# devkit.net
KiCad netlist of a schematic drawn in EAGLE
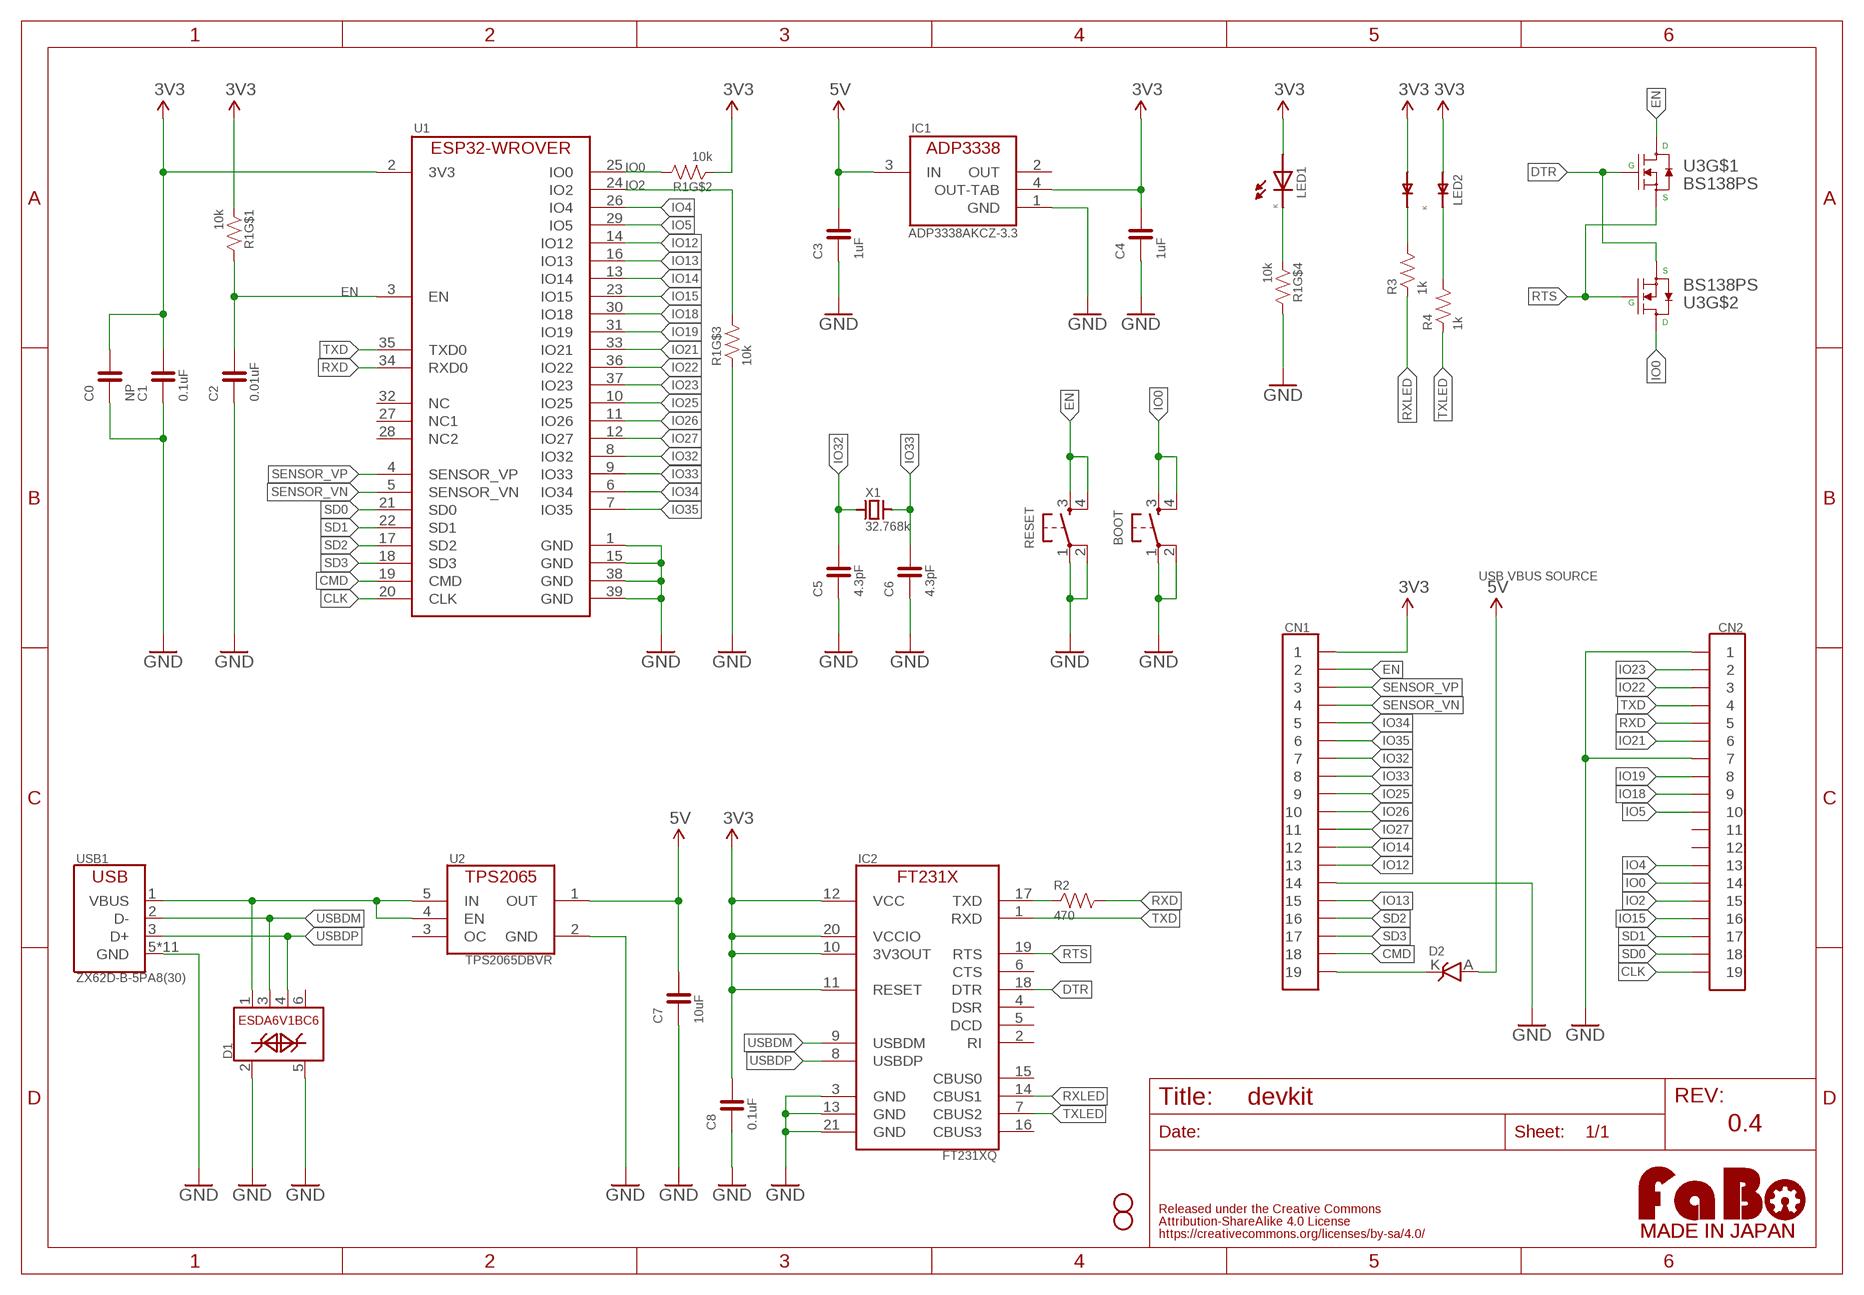
[diagram p0: schematic, sheet 1]

(export (version "E")
  (design (tool "Eeschema 10.0.6"))
  (components
    (comp (ref "BOOT")
      (value "TACTILE-KMR2")
      (footprint "eagle-import:KMR2-TACT")
      (libsource (lib "eagle-import") (part "TACTILE-KMR2"))
    )
    (comp (ref "C0")
      (value "NP")
      (footprint "eagle-import:MULTIPAD0603")
      (libsource (lib "eagle-import") (part "CAPACITOR-M"))
    )
    (comp (ref "C1")
      (value "0.1uF")
      (footprint "eagle-import:EIA0603")
      (libsource (lib "eagle-import") (part "CAPACITOR-0603"))
    )
    (comp (ref "C2")
      (value "0.01uF")
      (footprint "eagle-import:EIA0603")
      (libsource (lib "eagle-import") (part "CAPACITOR-0603"))
    )
    (comp (ref "C3")
      (value "1uF")
      (footprint "eagle-import:EIA0603")
      (libsource (lib "eagle-import") (part "CAPACITOR-0603"))
    )
    (comp (ref "C4")
      (value "1uF")
      (footprint "eagle-import:EIA0603")
      (libsource (lib "eagle-import") (part "CAPACITOR-0603"))
    )
    (comp (ref "C5")
      (value "4.3pF")
      (footprint "eagle-import:EIA0603")
      (libsource (lib "eagle-import") (part "CAPACITOR-0603"))
    )
    (comp (ref "C6")
      (value "4.3pF")
      (footprint "eagle-import:EIA0603")
      (libsource (lib "eagle-import") (part "CAPACITOR-0603"))
    )
    (comp (ref "C7")
      (value "10uF")
      (footprint "eagle-import:EIA0603")
      (libsource (lib "eagle-import") (part "CAPACITOR-0603"))
    )
    (comp (ref "C8")
      (value "0.1uF")
      (footprint "eagle-import:EIA0603")
      (libsource (lib "eagle-import") (part "CAPACITOR-0603"))
    )
    (comp (ref "CN1")
      (value "PIN_1X19")
      (footprint "eagle-import:PIN_1X19")
      (libsource (lib "eagle-import") (part "PIN_1X19"))
    )
    (comp (ref "CN2")
      (value "PIN_1X19")
      (footprint "eagle-import:PIN_1X19")
      (libsource (lib "eagle-import") (part "PIN_1X19"))
    )
    (comp (ref "D1")
      (value "ESDA6V1BC6")
      (footprint "eagle-import:SOT-23-6L")
      (libsource (lib "eagle-import") (part "ESDA6V1BC6"))
    )
    (comp (ref "D2")
      (value "DIODE_SCHOTTKY-RB161MM-20")
      (footprint "eagle-import:SOD-123FL_RB161MM-20")
      (libsource (lib "eagle-import") (part "DIODE_SCHOTTKY-RB161MM-20"))
    )
    (comp (ref "FID1")
      (value "FIDUCIAL-TOP")
      (footprint "eagle-import:FIDUCIAL_15_TOP")
      (libsource (lib "eagle-import") (part "FIDUCIAL-TOP"))
    )
    (comp (ref "FID2")
      (value "FIDUCIAL-TOP")
      (footprint "eagle-import:FIDUCIAL_15_TOP")
      (libsource (lib "eagle-import") (part "FIDUCIAL-TOP"))
    )
    (comp (ref "IC1")
      (value "ADP3338AKCZ-3.3")
      (footprint "eagle-import:SOT-223-KC3")
      (libsource (lib "eagle-import") (part "ADP3338AKCZ"))
    )
    (comp (ref "IC2")
      (value "FT231XQ")
      (footprint "eagle-import:QFN-20")
      (libsource (lib "eagle-import") (part "FT231XQ"))
    )
    (comp (ref "LED1")
      (value "LED-0603")
      (footprint "eagle-import:LED_0603")
      (libsource (lib "eagle-import") (part "LED-0603"))
    )
    (comp (ref "LED2")
      (value "HSMF-C16X")
      (footprint "eagle-import:HSMF-C16X")
      (libsource (lib "eagle-import") (part "HSMF-C16X"))
    )
    (comp (ref "LOGO1")
      (value "LOGO_FABO-M_BOTTOM")
      (footprint "eagle-import:LOGO_FABO_M_BOTTOM")
      (libsource (lib "eagle-import") (part "LOGO_FABO-M_BOTTOM"))
    )
    (comp (ref "R1")
      (value "10k")
      (footprint "eagle-import:EXBV8V")
      (libsource (lib "eagle-import") (part "RESISTOR_ARRAY"))
    )
    (comp (ref "R2")
      (value "470")
      (footprint "eagle-import:EIA0603")
      (libsource (lib "eagle-import") (part "RESISTOR-0603"))
    )
    (comp (ref "R3")
      (value "1k")
      (footprint "eagle-import:EIA0603")
      (libsource (lib "eagle-import") (part "RESISTOR-0603"))
    )
    (comp (ref "R4")
      (value "1k")
      (footprint "eagle-import:EIA0603")
      (libsource (lib "eagle-import") (part "RESISTOR-0603"))
    )
    (comp (ref "RESET")
      (value "TACTILE-KMR2")
      (footprint "eagle-import:KMR2-TACT")
      (libsource (lib "eagle-import") (part "TACTILE-KMR2"))
    )
    (comp (ref "U1")
      (value "ESP32-WROVER-B")
      (footprint "eagle-import:ESP32-WROVER-B")
      (libsource (lib "eagle-import") (part "ESP32-WROVER-B"))
    )
    (comp (ref "U2")
      (value "TPS2065DBVR")
      (footprint "eagle-import:SOT-23-5")
      (libsource (lib "eagle-import") (part "TPS2065DBV"))
    )
    (comp (ref "U3")
      (value "BS138PS")
      (footprint "eagle-import:SOT-363")
      (libsource (lib "eagle-import") (part "BS138PS"))
    )
    (comp (ref "USB1")
      (value "ZX62D-B-5PA8(30)")
      (footprint "eagle-import:ZX62D-B-5PA8")
      (libsource (lib "eagle-import") (part "USB-ZX62D"))
    )
    (comp (ref "X1")
      (value "32.768k")
      (footprint "eagle-import:ABS07")
      (libsource (lib "eagle-import") (part "CRYSTAL-ABS07"))
    )
  )
  (nets
    (net (code "1") (name "3V3") (class "Default")
      (node (ref "C0") (pin "2") (pinfunction "2_2") (pintype "passive"))
      (node (ref "C1") (pin "2") (pinfunction "2_2") (pintype "passive"))
      (node (ref "C4") (pin "2") (pinfunction "2_2") (pintype "passive"))
      (node (ref "C8") (pin "2") (pinfunction "2_2") (pintype "passive"))
      (node (ref "CN1") (pin "1") (pinfunction "1_1") (pintype "bidirectional"))
      (node (ref "IC1") (pin "4") (pinfunction "OUT-TAB_4") (pintype "bidirectional"))
      (node (ref "IC2") (pin "10") (pinfunction "3V3OUT_10") (pintype "bidirectional"))
      (node (ref "IC2") (pin "11") (pinfunction "RESET_11") (pintype "bidirectional"))
      (node (ref "IC2") (pin "12") (pinfunction "VCC_12") (pintype "bidirectional"))
      (node (ref "IC2") (pin "20") (pinfunction "VCCIO_20") (pintype "bidirectional"))
      (node (ref "LED1") (pin "A") (pinfunction "ANODE_A") (pintype "passive"))
      (node (ref "LED2") (pin "1") (pinfunction "A1_1") (pintype "passive"))
      (node (ref "LED2") (pin "2") (pinfunction "A2_2") (pintype "bidirectional"))
      (node (ref "R1") (pin "1") (pinfunction "1_1") (pintype "bidirectional"))
      (node (ref "R1") (pin "2") (pinfunction "1_2") (pintype "bidirectional"))
      (node (ref "U1") (pin "2") (pinfunction "3V3_2") (pintype "bidirectional"))
    )
    (net (code "2") (name "5V") (class "Default")
      (node (ref "C3") (pin "2") (pinfunction "2_2") (pintype "passive"))
      (node (ref "C7") (pin "2") (pinfunction "2_2") (pintype "passive"))
      (node (ref "D2") (pin "A") (pinfunction "A_A") (pintype "bidirectional"))
      (node (ref "IC1") (pin "3") (pinfunction "IN_3") (pintype "bidirectional"))
      (node (ref "U2") (pin "1") (pinfunction "OUT_1") (pintype "bidirectional"))
    )
    (net (code "3") (name "CLK") (class "Default")
      (node (ref "CN2") (pin "19") (pinfunction "19_19") (pintype "bidirectional"))
      (node (ref "U1") (pin "20") (pinfunction "CLK_20") (pintype "bidirectional"))
    )
    (net (code "4") (name "CMD") (class "Default")
      (node (ref "CN1") (pin "18") (pinfunction "18_18") (pintype "bidirectional"))
      (node (ref "U1") (pin "19") (pinfunction "CMD_19") (pintype "bidirectional"))
    )
    (net (code "5") (name "DTR") (class "Default")
      (node (ref "IC2") (pin "18") (pinfunction "DTR_18") (pintype "bidirectional"))
      (node (ref "U3") (pin "2") (pinfunction "G_2") (pintype "passive"))
      (node (ref "U3") (pin "4") (pinfunction "S_4") (pintype "passive"))
    )
    (net (code "6") (name "EN") (class "Default")
      (node (ref "C2") (pin "2") (pinfunction "2_2") (pintype "passive"))
      (node (ref "CN1") (pin "2") (pinfunction "2_2") (pintype "bidirectional"))
      (node (ref "R1") (pin "8") (pinfunction "2_8") (pintype "bidirectional"))
      (node (ref "RESET") (pin "3") (pinfunction "3_3") (pintype "passive"))
      (node (ref "RESET") (pin "4") (pinfunction "4_4") (pintype "passive"))
      (node (ref "U1") (pin "3") (pinfunction "EN_3") (pintype "bidirectional"))
      (node (ref "U3") (pin "6") (pinfunction "D_6") (pintype "passive"))
    )
    (net (code "7") (name "GND") (class "Default")
      (node (ref "BOOT") (pin "1") (pinfunction "1_1") (pintype "passive"))
      (node (ref "BOOT") (pin "2") (pinfunction "2_2") (pintype "passive"))
      (node (ref "C0") (pin "1") (pinfunction "1_1") (pintype "passive"))
      (node (ref "C1") (pin "1") (pinfunction "1_1") (pintype "passive"))
      (node (ref "C2") (pin "1") (pinfunction "1_1") (pintype "passive"))
      (node (ref "C3") (pin "1") (pinfunction "1_1") (pintype "passive"))
      (node (ref "C4") (pin "1") (pinfunction "1_1") (pintype "passive"))
      (node (ref "C5") (pin "1") (pinfunction "1_1") (pintype "passive"))
      (node (ref "C6") (pin "1") (pinfunction "1_1") (pintype "passive"))
      (node (ref "C7") (pin "1") (pinfunction "1_1") (pintype "passive"))
      (node (ref "C8") (pin "1") (pinfunction "1_1") (pintype "passive"))
      (node (ref "CN1") (pin "14") (pinfunction "14_14") (pintype "bidirectional"))
      (node (ref "CN2") (pin "1") (pinfunction "1_1") (pintype "bidirectional"))
      (node (ref "CN2") (pin "7") (pinfunction "7_7") (pintype "bidirectional"))
      (node (ref "D1") (pin "2") (pinfunction "2_2") (pintype "bidirectional"))
      (node (ref "D1") (pin "5") (pinfunction "5_5") (pintype "bidirectional"))
      (node (ref "IC1") (pin "1") (pinfunction "GND_1") (pintype "bidirectional"))
      (node (ref "IC2") (pin "13") (pinfunction "GND_13") (pintype "bidirectional"))
      (node (ref "IC2") (pin "21") (pinfunction "GND_21") (pintype "bidirectional"))
      (node (ref "IC2") (pin "3") (pinfunction "GND_3") (pintype "bidirectional"))
      (node (ref "R1") (pin "3") (pinfunction "1_3") (pintype "bidirectional"))
      (node (ref "R1") (pin "5") (pinfunction "2_5") (pintype "bidirectional"))
      (node (ref "RESET") (pin "1") (pinfunction "1_1") (pintype "passive"))
      (node (ref "RESET") (pin "2") (pinfunction "2_2") (pintype "passive"))
      (node (ref "U1") (pin "1") (pinfunction "GND_1") (pintype "bidirectional"))
      (node (ref "U1") (pin "15") (pinfunction "GND_15") (pintype "bidirectional"))
      (node (ref "U1") (pin "38") (pinfunction "GND_38") (pintype "bidirectional"))
      (node (ref "U1") (pin "39") (pinfunction "GND_39") (pintype "bidirectional"))
      (node (ref "U2") (pin "2") (pinfunction "GND_2") (pintype "bidirectional"))
      (node (ref "USB1") (pin "5") (pinfunction "GND_5") (pintype "bidirectional"))
      (node (ref "USB1") (pin "B1") (pinfunction "GND_B1") (pintype "bidirectional"))
      (node (ref "USB1") (pin "B2") (pinfunction "GND_B2") (pintype "bidirectional"))
      (node (ref "USB1") (pin "B3") (pinfunction "GND_B3") (pintype "bidirectional"))
      (node (ref "USB1") (pin "B4") (pinfunction "GND_B4") (pintype "bidirectional"))
      (node (ref "USB1") (pin "T1") (pinfunction "GND_T1") (pintype "bidirectional"))
      (node (ref "USB1") (pin "T2") (pinfunction "GND_T2") (pintype "bidirectional"))
      (node (ref "USB1") (pin "T3") (pinfunction "GND_T3") (pintype "bidirectional"))
      (node (ref "USB1") (pin "T4") (pinfunction "GND_T4") (pintype "bidirectional"))
      (node (ref "USB1") (pin "T5") (pinfunction "GND_T5") (pintype "bidirectional"))
      (node (ref "USB1") (pin "T6") (pinfunction "GND_T6") (pintype "bidirectional"))
    )
    (net (code "8") (name "IO0") (class "Default")
      (node (ref "BOOT") (pin "3") (pinfunction "3_3") (pintype "passive"))
      (node (ref "BOOT") (pin "4") (pinfunction "4_4") (pintype "passive"))
      (node (ref "CN2") (pin "14") (pinfunction "14_14") (pintype "bidirectional"))
      (node (ref "R1") (pin "7") (pinfunction "2_7") (pintype "bidirectional"))
      (node (ref "U1") (pin "25") (pinfunction "IO0_25") (pintype "bidirectional"))
      (node (ref "U3") (pin "3") (pinfunction "D_3") (pintype "passive"))
    )
    (net (code "9") (name "IO2") (class "Default")
      (node (ref "CN2") (pin "15") (pinfunction "15_15") (pintype "bidirectional"))
      (node (ref "R1") (pin "6") (pinfunction "2_6") (pintype "bidirectional"))
      (node (ref "U1") (pin "24") (pinfunction "IO2_24") (pintype "bidirectional"))
    )
    (net (code "10") (name "IO4") (class "Default")
      (node (ref "CN2") (pin "13") (pinfunction "13_13") (pintype "bidirectional"))
      (node (ref "U1") (pin "26") (pinfunction "IO4_26") (pintype "bidirectional"))
    )
    (net (code "11") (name "IO5") (class "Default")
      (node (ref "CN2") (pin "10") (pinfunction "10_10") (pintype "bidirectional"))
      (node (ref "U1") (pin "29") (pinfunction "IO5_29") (pintype "bidirectional"))
    )
    (net (code "12") (name "IO12") (class "Default")
      (node (ref "CN1") (pin "13") (pinfunction "13_13") (pintype "bidirectional"))
      (node (ref "U1") (pin "14") (pinfunction "IO12_14") (pintype "bidirectional"))
    )
    (net (code "13") (name "IO13") (class "Default")
      (node (ref "CN1") (pin "15") (pinfunction "15_15") (pintype "bidirectional"))
      (node (ref "U1") (pin "16") (pinfunction "IO13_16") (pintype "bidirectional"))
    )
    (net (code "14") (name "IO14") (class "Default")
      (node (ref "CN1") (pin "12") (pinfunction "12_12") (pintype "bidirectional"))
      (node (ref "U1") (pin "13") (pinfunction "IO14_13") (pintype "bidirectional"))
    )
    (net (code "15") (name "IO15") (class "Default")
      (node (ref "CN2") (pin "16") (pinfunction "16_16") (pintype "bidirectional"))
      (node (ref "U1") (pin "23") (pinfunction "IO15_23") (pintype "bidirectional"))
    )
    (net (code "16") (name "IO18") (class "Default")
      (node (ref "CN2") (pin "9") (pinfunction "9_9") (pintype "bidirectional"))
      (node (ref "U1") (pin "30") (pinfunction "IO18_30") (pintype "bidirectional"))
    )
    (net (code "17") (name "IO19") (class "Default")
      (node (ref "CN2") (pin "8") (pinfunction "8_8") (pintype "bidirectional"))
      (node (ref "U1") (pin "31") (pinfunction "IO19_31") (pintype "bidirectional"))
    )
    (net (code "18") (name "IO21") (class "Default")
      (node (ref "CN2") (pin "6") (pinfunction "6_6") (pintype "bidirectional"))
      (node (ref "U1") (pin "33") (pinfunction "IO21_33") (pintype "bidirectional"))
    )
    (net (code "19") (name "IO22") (class "Default")
      (node (ref "CN2") (pin "3") (pinfunction "3_3") (pintype "bidirectional"))
      (node (ref "U1") (pin "36") (pinfunction "IO22_36") (pintype "bidirectional"))
    )
    (net (code "20") (name "IO23") (class "Default")
      (node (ref "CN2") (pin "2") (pinfunction "2_2") (pintype "bidirectional"))
      (node (ref "U1") (pin "37") (pinfunction "IO23_37") (pintype "bidirectional"))
    )
    (net (code "21") (name "IO25") (class "Default")
      (node (ref "CN1") (pin "9") (pinfunction "9_9") (pintype "bidirectional"))
      (node (ref "U1") (pin "10") (pinfunction "IO25_10") (pintype "bidirectional"))
    )
    (net (code "22") (name "IO26") (class "Default")
      (node (ref "CN1") (pin "10") (pinfunction "10_10") (pintype "bidirectional"))
      (node (ref "U1") (pin "11") (pinfunction "IO26_11") (pintype "bidirectional"))
    )
    (net (code "23") (name "IO27") (class "Default")
      (node (ref "CN1") (pin "11") (pinfunction "11_11") (pintype "bidirectional"))
      (node (ref "U1") (pin "12") (pinfunction "IO27_12") (pintype "bidirectional"))
    )
    (net (code "24") (name "IO32") (class "Default")
      (node (ref "C5") (pin "2") (pinfunction "2_2") (pintype "passive"))
      (node (ref "CN1") (pin "7") (pinfunction "7_7") (pintype "bidirectional"))
      (node (ref "U1") (pin "8") (pinfunction "IO32_8") (pintype "bidirectional"))
      (node (ref "X1") (pin "1") (pinfunction "P$1_1") (pintype "bidirectional"))
    )
    (net (code "25") (name "IO33") (class "Default")
      (node (ref "C6") (pin "2") (pinfunction "2_2") (pintype "passive"))
      (node (ref "CN1") (pin "8") (pinfunction "8_8") (pintype "bidirectional"))
      (node (ref "U1") (pin "9") (pinfunction "IO33_9") (pintype "bidirectional"))
      (node (ref "X1") (pin "2") (pinfunction "P$2_2") (pintype "bidirectional"))
    )
    (net (code "26") (name "IO34") (class "Default")
      (node (ref "CN1") (pin "5") (pinfunction "5_5") (pintype "bidirectional"))
      (node (ref "U1") (pin "6") (pinfunction "IO34_6") (pintype "bidirectional"))
    )
    (net (code "27") (name "IO35") (class "Default")
      (node (ref "CN1") (pin "6") (pinfunction "6_6") (pintype "bidirectional"))
      (node (ref "U1") (pin "7") (pinfunction "IO35_7") (pintype "bidirectional"))
    )
    (net (code "28") (name "Net-(CN1-Pad19)") (class "Default")
      (node (ref "CN1") (pin "19") (pinfunction "19_19") (pintype "bidirectional"))
      (node (ref "D2") (pin "K") (pinfunction "K_K") (pintype "bidirectional"))
    )
    (net (code "29") (name "Net-(IC2-TXD)") (class "Default")
      (node (ref "IC2") (pin "17") (pinfunction "TXD_17") (pintype "bidirectional"))
      (node (ref "R2") (pin "1") (pinfunction "1_1") (pintype "bidirectional"))
    )
    (net (code "30") (name "Net-(LED1-CATHODE)") (class "Default")
      (node (ref "LED1") (pin "K") (pinfunction "CATHODE_K") (pintype "passive"))
      (node (ref "R1") (pin "4") (pinfunction "1_4") (pintype "bidirectional"))
    )
    (net (code "31") (name "Net-(LED2-K1)") (class "Default")
      (node (ref "LED2") (pin "3") (pinfunction "K1_3") (pintype "passive"))
      (node (ref "R4") (pin "2") (pinfunction "2_2") (pintype "bidirectional"))
    )
    (net (code "32") (name "Net-(LED2-K2)") (class "Default")
      (node (ref "LED2") (pin "4") (pinfunction "K2_4") (pintype "bidirectional"))
      (node (ref "R3") (pin "2") (pinfunction "2_2") (pintype "bidirectional"))
    )
    (net (code "33") (name "Net-(U2-EN)") (class "Default")
      (node (ref "D1") (pin "1") (pinfunction "1_1") (pintype "bidirectional"))
      (node (ref "U2") (pin "4") (pinfunction "EN_4") (pintype "bidirectional"))
      (node (ref "U2") (pin "5") (pinfunction "IN_5") (pintype "bidirectional"))
      (node (ref "USB1") (pin "1") (pinfunction "VBUS_1") (pintype "bidirectional"))
    )
    (net (code "34") (name "RTS") (class "Default")
      (node (ref "IC2") (pin "19") (pinfunction "RTS_19") (pintype "bidirectional"))
      (node (ref "U3") (pin "1") (pinfunction "S_1") (pintype "passive"))
      (node (ref "U3") (pin "5") (pinfunction "G_5") (pintype "passive"))
    )
    (net (code "35") (name "RXD") (class "Default")
      (node (ref "CN2") (pin "5") (pinfunction "5_5") (pintype "bidirectional"))
      (node (ref "R2") (pin "2") (pinfunction "2_2") (pintype "bidirectional"))
      (node (ref "U1") (pin "34") (pinfunction "RXD0_34") (pintype "bidirectional"))
    )
    (net (code "36") (name "RXLED") (class "Default")
      (node (ref "IC2") (pin "14") (pinfunction "CBUS1_14") (pintype "bidirectional"))
      (node (ref "R3") (pin "1") (pinfunction "1_1") (pintype "bidirectional"))
    )
    (net (code "37") (name "SD0") (class "Default")
      (node (ref "CN2") (pin "18") (pinfunction "18_18") (pintype "bidirectional"))
      (node (ref "U1") (pin "21") (pinfunction "SD0_21") (pintype "bidirectional"))
    )
    (net (code "38") (name "SD1") (class "Default")
      (node (ref "CN2") (pin "17") (pinfunction "17_17") (pintype "bidirectional"))
      (node (ref "U1") (pin "22") (pinfunction "SD1_22") (pintype "bidirectional"))
    )
    (net (code "39") (name "SD2") (class "Default")
      (node (ref "CN1") (pin "16") (pinfunction "16_16") (pintype "bidirectional"))
      (node (ref "U1") (pin "17") (pinfunction "SD2_17") (pintype "bidirectional"))
    )
    (net (code "40") (name "SD3") (class "Default")
      (node (ref "CN1") (pin "17") (pinfunction "17_17") (pintype "bidirectional"))
      (node (ref "U1") (pin "18") (pinfunction "SD3_18") (pintype "bidirectional"))
    )
    (net (code "41") (name "SENSOR_VN") (class "Default")
      (node (ref "CN1") (pin "4") (pinfunction "4_4") (pintype "bidirectional"))
      (node (ref "U1") (pin "5") (pinfunction "SENSOR_VN_5") (pintype "bidirectional"))
    )
    (net (code "42") (name "SENSOR_VP") (class "Default")
      (node (ref "CN1") (pin "3") (pinfunction "3_3") (pintype "bidirectional"))
      (node (ref "U1") (pin "4") (pinfunction "SENSOR_VP_4") (pintype "bidirectional"))
    )
    (net (code "43") (name "TXD") (class "Default")
      (node (ref "CN2") (pin "4") (pinfunction "4_4") (pintype "bidirectional"))
      (node (ref "IC2") (pin "1") (pinfunction "RXD_1") (pintype "bidirectional"))
      (node (ref "U1") (pin "35") (pinfunction "TXD0_35") (pintype "bidirectional"))
    )
    (net (code "44") (name "TXLED") (class "Default")
      (node (ref "IC2") (pin "7") (pinfunction "CBUS2_7") (pintype "bidirectional"))
      (node (ref "R4") (pin "1") (pinfunction "1_1") (pintype "bidirectional"))
    )
    (net (code "45") (name "USBDM") (class "Default")
      (node (ref "D1") (pin "3") (pinfunction "3_3") (pintype "bidirectional"))
      (node (ref "IC2") (pin "9") (pinfunction "USBDM_9") (pintype "bidirectional"))
      (node (ref "USB1") (pin "2") (pinfunction "D-_2") (pintype "bidirectional"))
    )
    (net (code "46") (name "USBDP") (class "Default")
      (node (ref "D1") (pin "4") (pinfunction "4_4") (pintype "bidirectional"))
      (node (ref "IC2") (pin "8") (pinfunction "USBDP_8") (pintype "bidirectional"))
      (node (ref "USB1") (pin "3") (pinfunction "D+_3") (pintype "bidirectional"))
    )
    (net (code "47") (name "unconnected-(CN2-Pad11)") (class "Default")
      (node (ref "CN2") (pin "11") (pinfunction "11_11") (pintype "bidirectional"))
    )
    (net (code "48") (name "unconnected-(CN2-Pad12)") (class "Default")
      (node (ref "CN2") (pin "12") (pinfunction "12_12") (pintype "bidirectional"))
    )
    (net (code "49") (name "unconnected-(D1-Pad6)") (class "Default")
      (node (ref "D1") (pin "6") (pinfunction "6_6") (pintype "bidirectional"))
    )
    (net (code "50") (name "unconnected-(IC1-OUT-Pad2)") (class "Default")
      (node (ref "IC1") (pin "2") (pinfunction "OUT_2") (pintype "bidirectional"))
    )
    (net (code "51") (name "unconnected-(IC2-CBUS0-Pad15)") (class "Default")
      (node (ref "IC2") (pin "15") (pinfunction "CBUS0_15") (pintype "bidirectional"))
    )
    (net (code "52") (name "unconnected-(IC2-CBUS3-Pad16)") (class "Default")
      (node (ref "IC2") (pin "16") (pinfunction "CBUS3_16") (pintype "bidirectional"))
    )
    (net (code "53") (name "unconnected-(IC2-CTS-Pad6)") (class "Default")
      (node (ref "IC2") (pin "6") (pinfunction "CTS_6") (pintype "bidirectional"))
    )
    (net (code "54") (name "unconnected-(IC2-DCD-Pad5)") (class "Default")
      (node (ref "IC2") (pin "5") (pinfunction "DCD_5") (pintype "bidirectional"))
    )
    (net (code "55") (name "unconnected-(IC2-DSR-Pad4)") (class "Default")
      (node (ref "IC2") (pin "4") (pinfunction "DSR_4") (pintype "bidirectional"))
    )
    (net (code "56") (name "unconnected-(IC2-RI-Pad2)") (class "Default")
      (node (ref "IC2") (pin "2") (pinfunction "RI_2") (pintype "bidirectional"))
    )
    (net (code "57") (name "unconnected-(U1-NC-Pad32)") (class "Default")
      (node (ref "U1") (pin "32") (pinfunction "NC_32") (pintype "bidirectional"))
    )
    (net (code "58") (name "unconnected-(U1-NC1-Pad27)") (class "Default")
      (node (ref "U1") (pin "27") (pinfunction "NC1_27") (pintype "bidirectional"))
    )
    (net (code "59") (name "unconnected-(U1-NC2-Pad28)") (class "Default")
      (node (ref "U1") (pin "28") (pinfunction "NC2_28") (pintype "bidirectional"))
    )
    (net (code "60") (name "unconnected-(U2-OC-Pad3)") (class "Default")
      (node (ref "U2") (pin "3") (pinfunction "OC_3") (pintype "bidirectional"))
    )
  )
)
